# LED_Sensor_Board.net
KiCad netlist of a schematic drawn in EAGLE
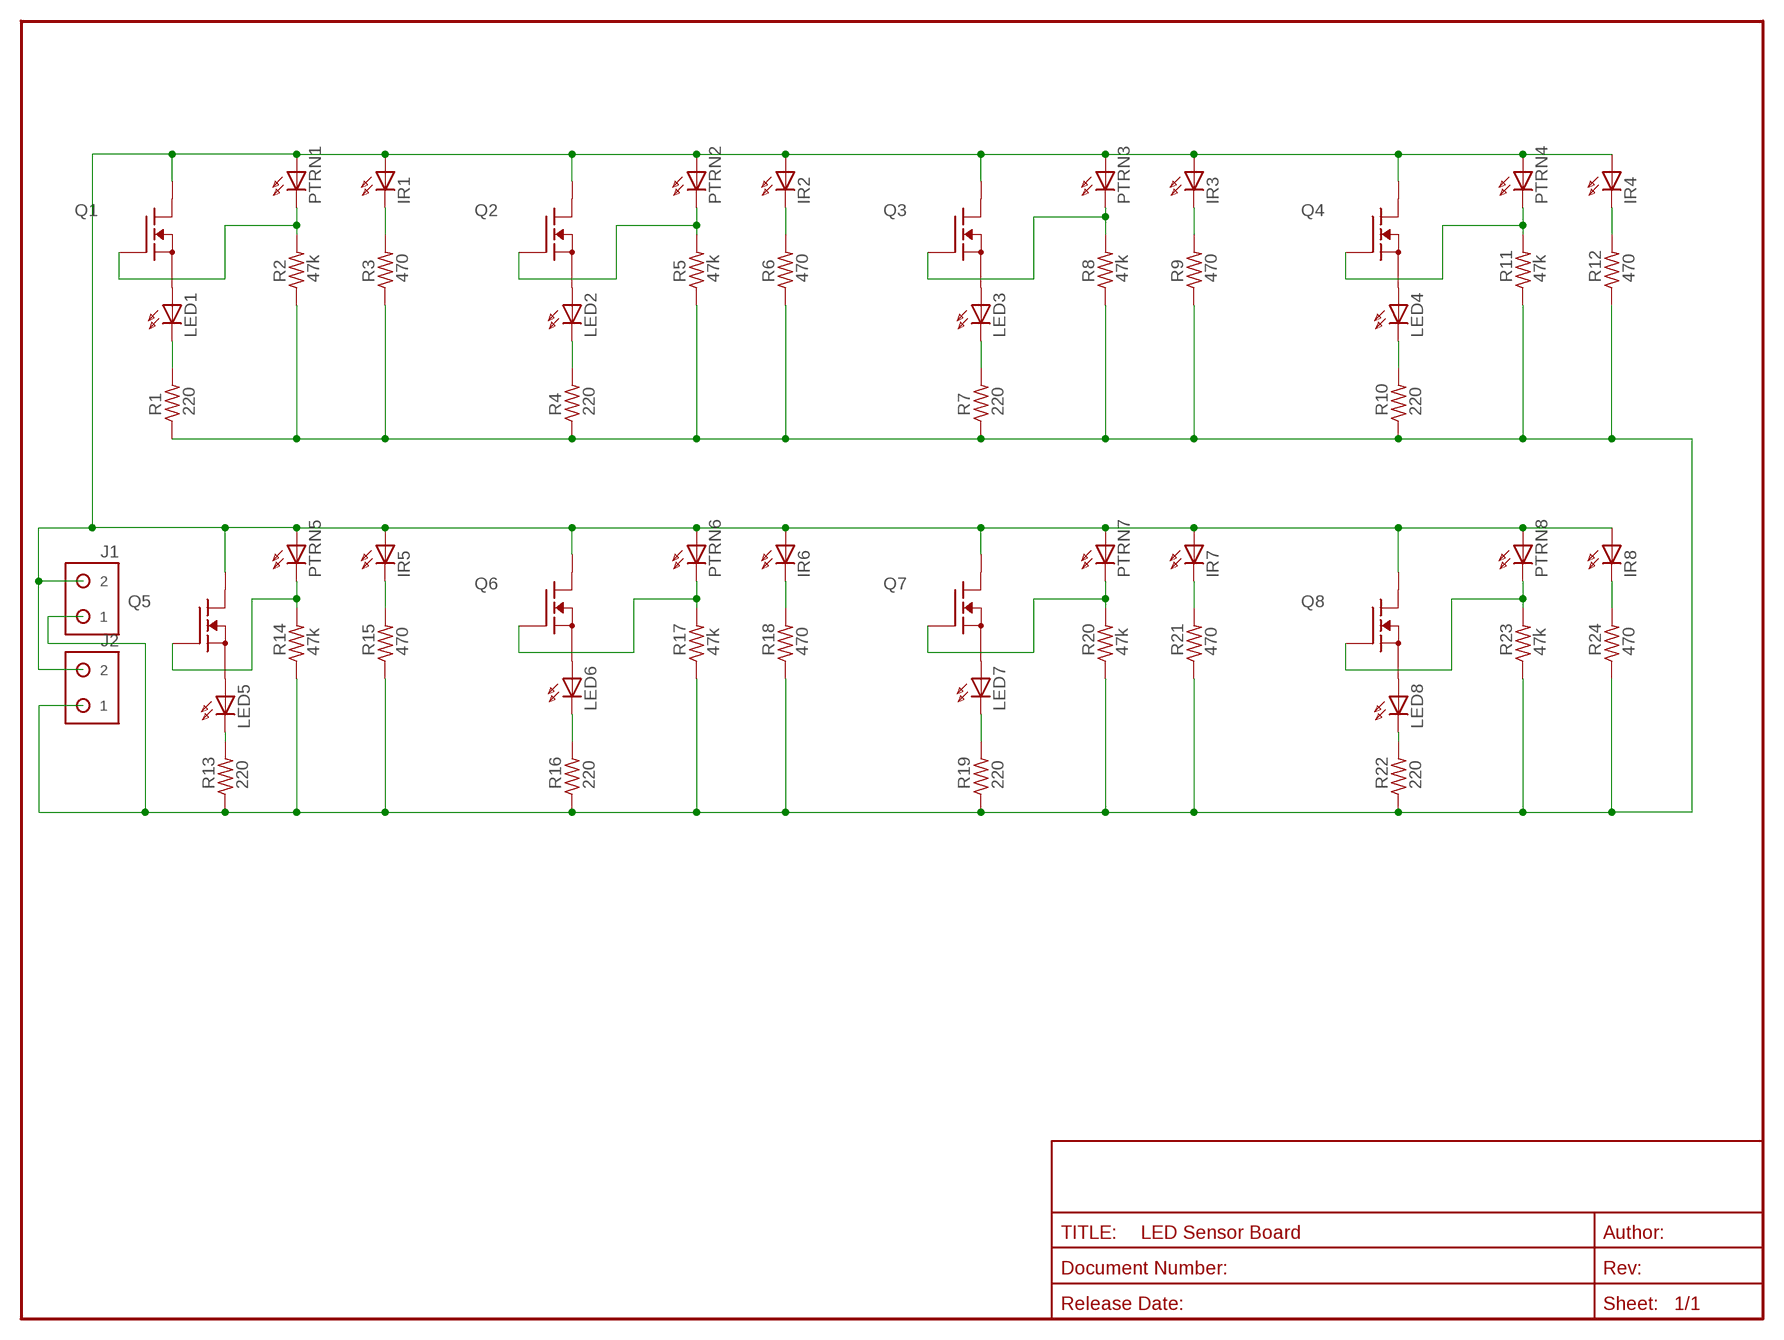
[diagram p0: schematic, sheet 1]

(export (version "E")
  (design (tool "Eeschema 10.0.6"))
  (components
    (comp (ref "IR1")
      (value "LED-T1-3/4")
      (footprint "eagle-import:LED-5MM")
      (libsource (lib "eagle-import") (part "LED-T1-3/4"))
    )
    (comp (ref "IR2")
      (value "LED-T1-3/4")
      (footprint "eagle-import:LED-5MM")
      (libsource (lib "eagle-import") (part "LED-T1-3/4"))
    )
    (comp (ref "IR3")
      (value "LED-T1-3/4")
      (footprint "eagle-import:LED-5MM")
      (libsource (lib "eagle-import") (part "LED-T1-3/4"))
    )
    (comp (ref "IR4")
      (value "LED-T1-3/4")
      (footprint "eagle-import:LED-5MM")
      (libsource (lib "eagle-import") (part "LED-T1-3/4"))
    )
    (comp (ref "IR5")
      (value "LED-T1-3/4")
      (footprint "eagle-import:LED-5MM")
      (libsource (lib "eagle-import") (part "LED-T1-3/4"))
    )
    (comp (ref "IR6")
      (value "LED-T1-3/4")
      (footprint "eagle-import:LED-5MM")
      (libsource (lib "eagle-import") (part "LED-T1-3/4"))
    )
    (comp (ref "IR7")
      (value "LED-T1-3/4")
      (footprint "eagle-import:LED-5MM")
      (libsource (lib "eagle-import") (part "LED-T1-3/4"))
    )
    (comp (ref "IR8")
      (value "LED-T1-3/4")
      (footprint "eagle-import:LED-5MM")
      (libsource (lib "eagle-import") (part "LED-T1-3/4"))
    )
    (comp (ref "J1")
      (value "HDR-1X2")
      (footprint "eagle-import:HDR-1X2")
      (libsource (lib "eagle-import") (part "HDR-1X2"))
    )
    (comp (ref "J2")
      (value "HDR-1X2")
      (footprint "eagle-import:HDR-1X2")
      (libsource (lib "eagle-import") (part "HDR-1X2"))
    )
    (comp (ref "LED1")
      (value "LED-T1-3/4")
      (footprint "eagle-import:LED-5MM")
      (libsource (lib "eagle-import") (part "LED-T1-3/4"))
    )
    (comp (ref "LED2")
      (value "LED-T1-3/4")
      (footprint "eagle-import:LED-5MM")
      (libsource (lib "eagle-import") (part "LED-T1-3/4"))
    )
    (comp (ref "LED3")
      (value "LED-T1-3/4")
      (footprint "eagle-import:LED-5MM")
      (libsource (lib "eagle-import") (part "LED-T1-3/4"))
    )
    (comp (ref "LED4")
      (value "LED-T1-3/4")
      (footprint "eagle-import:LED-5MM")
      (libsource (lib "eagle-import") (part "LED-T1-3/4"))
    )
    (comp (ref "LED5")
      (value "LED-T1-3/4")
      (footprint "eagle-import:LED-5MM")
      (libsource (lib "eagle-import") (part "LED-T1-3/4"))
    )
    (comp (ref "LED6")
      (value "LED-T1-3/4")
      (footprint "eagle-import:LED-5MM")
      (libsource (lib "eagle-import") (part "LED-T1-3/4"))
    )
    (comp (ref "LED7")
      (value "LED-T1-3/4")
      (footprint "eagle-import:LED-5MM")
      (libsource (lib "eagle-import") (part "LED-T1-3/4"))
    )
    (comp (ref "LED8")
      (value "LED-T1-3/4")
      (footprint "eagle-import:LED-5MM")
      (libsource (lib "eagle-import") (part "LED-T1-3/4"))
    )
    (comp (ref "PTRN1")
      (value "LED-T1-3/4")
      (footprint "eagle-import:LED-5MM")
      (libsource (lib "eagle-import") (part "LED-T1-3/4"))
    )
    (comp (ref "PTRN2")
      (value "LED-T1-3/4")
      (footprint "eagle-import:LED-5MM")
      (libsource (lib "eagle-import") (part "LED-T1-3/4"))
    )
    (comp (ref "PTRN3")
      (value "LED-T1-3/4")
      (footprint "eagle-import:LED-5MM")
      (libsource (lib "eagle-import") (part "LED-T1-3/4"))
    )
    (comp (ref "PTRN4")
      (value "LED-T1-3/4")
      (footprint "eagle-import:LED-5MM")
      (libsource (lib "eagle-import") (part "LED-T1-3/4"))
    )
    (comp (ref "PTRN5")
      (value "LED-T1-3/4")
      (footprint "eagle-import:LED-5MM")
      (libsource (lib "eagle-import") (part "LED-T1-3/4"))
    )
    (comp (ref "PTRN6")
      (value "LED-T1-3/4")
      (footprint "eagle-import:LED-5MM")
      (libsource (lib "eagle-import") (part "LED-T1-3/4"))
    )
    (comp (ref "PTRN7")
      (value "LED-T1-3/4")
      (footprint "eagle-import:LED-5MM")
      (libsource (lib "eagle-import") (part "LED-T1-3/4"))
    )
    (comp (ref "PTRN8")
      (value "LED-T1-3/4")
      (footprint "eagle-import:LED-5MM")
      (libsource (lib "eagle-import") (part "LED-T1-3/4"))
    )
    (comp (ref "Q1")
      (value "ZVN2110A")
      (footprint "eagle-import:TO92-")
      (libsource (lib "eagle-import") (part "ZVN2110A"))
    )
    (comp (ref "Q2")
      (value "ZVN2110A")
      (footprint "eagle-import:TO92-")
      (libsource (lib "eagle-import") (part "ZVN2110A"))
    )
    (comp (ref "Q3")
      (value "ZVN2110A")
      (footprint "eagle-import:TO92-")
      (libsource (lib "eagle-import") (part "ZVN2110A"))
    )
    (comp (ref "Q4")
      (value "ZVN2110A")
      (footprint "eagle-import:TO92-")
      (libsource (lib "eagle-import") (part "ZVN2110A"))
    )
    (comp (ref "Q5")
      (value "ZVN2110A")
      (footprint "eagle-import:TO92-")
      (libsource (lib "eagle-import") (part "ZVN2110A"))
    )
    (comp (ref "Q6")
      (value "ZVN2110A")
      (footprint "eagle-import:TO92-")
      (libsource (lib "eagle-import") (part "ZVN2110A"))
    )
    (comp (ref "Q7")
      (value "ZVN2110A")
      (footprint "eagle-import:TO92-")
      (libsource (lib "eagle-import") (part "ZVN2110A"))
    )
    (comp (ref "Q8")
      (value "ZVN2110A")
      (footprint "eagle-import:TO92-")
      (libsource (lib "eagle-import") (part "ZVN2110A"))
    )
    (comp (ref "R1")
      (value "220")
      (footprint "eagle-import:0207_10")
      (libsource (lib "eagle-import") (part "RES-0207/10"))
    )
    (comp (ref "R2")
      (value "47k")
      (footprint "eagle-import:0207_10")
      (libsource (lib "eagle-import") (part "RES-0207/10"))
    )
    (comp (ref "R3")
      (value "470")
      (footprint "eagle-import:0207_10")
      (libsource (lib "eagle-import") (part "RES-0207/10"))
    )
    (comp (ref "R4")
      (value "220")
      (footprint "eagle-import:0207_10")
      (libsource (lib "eagle-import") (part "RES-0207/10"))
    )
    (comp (ref "R5")
      (value "47k")
      (footprint "eagle-import:0207_10")
      (libsource (lib "eagle-import") (part "RES-0207/10"))
    )
    (comp (ref "R6")
      (value "470")
      (footprint "eagle-import:0207_10")
      (libsource (lib "eagle-import") (part "RES-0207/10"))
    )
    (comp (ref "R7")
      (value "220")
      (footprint "eagle-import:0207_10")
      (libsource (lib "eagle-import") (part "RES-0207/10"))
    )
    (comp (ref "R8")
      (value "47k")
      (footprint "eagle-import:0207_10")
      (libsource (lib "eagle-import") (part "RES-0207/10"))
    )
    (comp (ref "R9")
      (value "470")
      (footprint "eagle-import:0207_10")
      (libsource (lib "eagle-import") (part "RES-0207/10"))
    )
    (comp (ref "R10")
      (value "220")
      (footprint "eagle-import:0207_10")
      (libsource (lib "eagle-import") (part "RES-0207/10"))
    )
    (comp (ref "R11")
      (value "47k")
      (footprint "eagle-import:0207_10")
      (libsource (lib "eagle-import") (part "RES-0207/10"))
    )
    (comp (ref "R12")
      (value "470")
      (footprint "eagle-import:0207_10")
      (libsource (lib "eagle-import") (part "RES-0207/10"))
    )
    (comp (ref "R13")
      (value "220")
      (footprint "eagle-import:0207_10")
      (libsource (lib "eagle-import") (part "RES-0207/10"))
    )
    (comp (ref "R14")
      (value "47k")
      (footprint "eagle-import:0207_10")
      (libsource (lib "eagle-import") (part "RES-0207/10"))
    )
    (comp (ref "R15")
      (value "470")
      (footprint "eagle-import:0207_10")
      (libsource (lib "eagle-import") (part "RES-0207/10"))
    )
    (comp (ref "R16")
      (value "220")
      (footprint "eagle-import:0207_10")
      (libsource (lib "eagle-import") (part "RES-0207/10"))
    )
    (comp (ref "R17")
      (value "47k")
      (footprint "eagle-import:0207_10")
      (libsource (lib "eagle-import") (part "RES-0207/10"))
    )
    (comp (ref "R18")
      (value "470")
      (footprint "eagle-import:0207_10")
      (libsource (lib "eagle-import") (part "RES-0207/10"))
    )
    (comp (ref "R19")
      (value "220")
      (footprint "eagle-import:0207_10")
      (libsource (lib "eagle-import") (part "RES-0207/10"))
    )
    (comp (ref "R20")
      (value "47k")
      (footprint "eagle-import:0207_10")
      (libsource (lib "eagle-import") (part "RES-0207/10"))
    )
    (comp (ref "R21")
      (value "470")
      (footprint "eagle-import:0207_10")
      (libsource (lib "eagle-import") (part "RES-0207/10"))
    )
    (comp (ref "R22")
      (value "220")
      (footprint "eagle-import:0207_10")
      (libsource (lib "eagle-import") (part "RES-0207/10"))
    )
    (comp (ref "R23")
      (value "47k")
      (footprint "eagle-import:0207_10")
      (libsource (lib "eagle-import") (part "RES-0207/10"))
    )
    (comp (ref "R24")
      (value "470")
      (footprint "eagle-import:0207_10")
      (libsource (lib "eagle-import") (part "RES-0207/10"))
    )
  )
  (nets
    (net (code "1") (name "Net-(IR1-C)") (class "Default")
      (node (ref "IR1") (pin "K") (pinfunction "C_K") (pintype "passive"))
      (node (ref "R3") (pin "2") (pinfunction "2_2") (pintype "passive"))
    )
    (net (code "2") (name "Net-(IR2-C)") (class "Default")
      (node (ref "IR2") (pin "K") (pinfunction "C_K") (pintype "passive"))
      (node (ref "R6") (pin "2") (pinfunction "2_2") (pintype "passive"))
    )
    (net (code "3") (name "Net-(IR3-C)") (class "Default")
      (node (ref "IR3") (pin "K") (pinfunction "C_K") (pintype "passive"))
      (node (ref "R9") (pin "2") (pinfunction "2_2") (pintype "passive"))
    )
    (net (code "4") (name "Net-(IR4-C)") (class "Default")
      (node (ref "IR4") (pin "K") (pinfunction "C_K") (pintype "passive"))
      (node (ref "R12") (pin "2") (pinfunction "2_2") (pintype "passive"))
    )
    (net (code "5") (name "Net-(IR5-C)") (class "Default")
      (node (ref "IR5") (pin "K") (pinfunction "C_K") (pintype "passive"))
      (node (ref "R15") (pin "2") (pinfunction "2_2") (pintype "passive"))
    )
    (net (code "6") (name "Net-(IR6-C)") (class "Default")
      (node (ref "IR6") (pin "K") (pinfunction "C_K") (pintype "passive"))
      (node (ref "R18") (pin "2") (pinfunction "2_2") (pintype "passive"))
    )
    (net (code "7") (name "Net-(IR7-C)") (class "Default")
      (node (ref "IR7") (pin "K") (pinfunction "C_K") (pintype "passive"))
      (node (ref "R21") (pin "2") (pinfunction "2_2") (pintype "passive"))
    )
    (net (code "8") (name "Net-(IR8-C)") (class "Default")
      (node (ref "IR8") (pin "K") (pinfunction "C_K") (pintype "passive"))
      (node (ref "R24") (pin "2") (pinfunction "2_2") (pintype "passive"))
    )
    (net (code "9") (name "Net-(J1-Pad1)") (class "Default")
      (node (ref "J1") (pin "1") (pinfunction "1_1") (pintype "passive"))
      (node (ref "J2") (pin "1") (pinfunction "1_1") (pintype "passive"))
      (node (ref "R1") (pin "1") (pinfunction "1_1") (pintype "passive"))
      (node (ref "R10") (pin "1") (pinfunction "1_1") (pintype "passive"))
      (node (ref "R11") (pin "1") (pinfunction "1_1") (pintype "passive"))
      (node (ref "R12") (pin "1") (pinfunction "1_1") (pintype "passive"))
      (node (ref "R13") (pin "1") (pinfunction "1_1") (pintype "passive"))
      (node (ref "R14") (pin "1") (pinfunction "1_1") (pintype "passive"))
      (node (ref "R15") (pin "1") (pinfunction "1_1") (pintype "passive"))
      (node (ref "R16") (pin "1") (pinfunction "1_1") (pintype "passive"))
      (node (ref "R17") (pin "1") (pinfunction "1_1") (pintype "passive"))
      (node (ref "R18") (pin "1") (pinfunction "1_1") (pintype "passive"))
      (node (ref "R19") (pin "1") (pinfunction "1_1") (pintype "passive"))
      (node (ref "R2") (pin "1") (pinfunction "1_1") (pintype "passive"))
      (node (ref "R20") (pin "1") (pinfunction "1_1") (pintype "passive"))
      (node (ref "R21") (pin "1") (pinfunction "1_1") (pintype "passive"))
      (node (ref "R22") (pin "1") (pinfunction "1_1") (pintype "passive"))
      (node (ref "R23") (pin "1") (pinfunction "1_1") (pintype "passive"))
      (node (ref "R24") (pin "1") (pinfunction "1_1") (pintype "passive"))
      (node (ref "R3") (pin "1") (pinfunction "1_1") (pintype "passive"))
      (node (ref "R4") (pin "1") (pinfunction "1_1") (pintype "passive"))
      (node (ref "R5") (pin "1") (pinfunction "1_1") (pintype "passive"))
      (node (ref "R6") (pin "1") (pinfunction "1_1") (pintype "passive"))
      (node (ref "R7") (pin "1") (pinfunction "1_1") (pintype "passive"))
      (node (ref "R8") (pin "1") (pinfunction "1_1") (pintype "passive"))
      (node (ref "R9") (pin "1") (pinfunction "1_1") (pintype "passive"))
    )
    (net (code "10") (name "Net-(LED1-C)") (class "Default")
      (node (ref "LED1") (pin "K") (pinfunction "C_K") (pintype "passive"))
      (node (ref "R1") (pin "2") (pinfunction "2_2") (pintype "passive"))
    )
    (net (code "11") (name "Net-(LED2-C)") (class "Default")
      (node (ref "LED2") (pin "K") (pinfunction "C_K") (pintype "passive"))
      (node (ref "R4") (pin "2") (pinfunction "2_2") (pintype "passive"))
    )
    (net (code "12") (name "Net-(LED3-C)") (class "Default")
      (node (ref "LED3") (pin "K") (pinfunction "C_K") (pintype "passive"))
      (node (ref "R7") (pin "2") (pinfunction "2_2") (pintype "passive"))
    )
    (net (code "13") (name "Net-(LED4-C)") (class "Default")
      (node (ref "LED4") (pin "K") (pinfunction "C_K") (pintype "passive"))
      (node (ref "R10") (pin "2") (pinfunction "2_2") (pintype "passive"))
    )
    (net (code "14") (name "Net-(LED5-C)") (class "Default")
      (node (ref "LED5") (pin "K") (pinfunction "C_K") (pintype "passive"))
      (node (ref "R13") (pin "2") (pinfunction "2_2") (pintype "passive"))
    )
    (net (code "15") (name "Net-(LED6-C)") (class "Default")
      (node (ref "LED6") (pin "K") (pinfunction "C_K") (pintype "passive"))
      (node (ref "R16") (pin "2") (pinfunction "2_2") (pintype "passive"))
    )
    (net (code "16") (name "Net-(LED7-C)") (class "Default")
      (node (ref "LED7") (pin "K") (pinfunction "C_K") (pintype "passive"))
      (node (ref "R19") (pin "2") (pinfunction "2_2") (pintype "passive"))
    )
    (net (code "17") (name "Net-(LED8-C)") (class "Default")
      (node (ref "LED8") (pin "K") (pinfunction "C_K") (pintype "passive"))
      (node (ref "R22") (pin "2") (pinfunction "2_2") (pintype "passive"))
    )
    (net (code "18") (name "Net-(PTRN1-C)") (class "Default")
      (node (ref "PTRN1") (pin "K") (pinfunction "C_K") (pintype "passive"))
      (node (ref "Q1") (pin "2") (pinfunction "G_2") (pintype "passive"))
      (node (ref "R2") (pin "2") (pinfunction "2_2") (pintype "passive"))
    )
    (net (code "19") (name "Net-(PTRN2-C)") (class "Default")
      (node (ref "PTRN2") (pin "K") (pinfunction "C_K") (pintype "passive"))
      (node (ref "Q2") (pin "2") (pinfunction "G_2") (pintype "passive"))
      (node (ref "R5") (pin "2") (pinfunction "2_2") (pintype "passive"))
    )
    (net (code "20") (name "Net-(PTRN3-C)") (class "Default")
      (node (ref "PTRN3") (pin "K") (pinfunction "C_K") (pintype "passive"))
      (node (ref "Q3") (pin "2") (pinfunction "G_2") (pintype "passive"))
      (node (ref "R8") (pin "2") (pinfunction "2_2") (pintype "passive"))
    )
    (net (code "21") (name "Net-(PTRN4-C)") (class "Default")
      (node (ref "PTRN4") (pin "K") (pinfunction "C_K") (pintype "passive"))
      (node (ref "Q4") (pin "2") (pinfunction "G_2") (pintype "passive"))
      (node (ref "R11") (pin "2") (pinfunction "2_2") (pintype "passive"))
    )
    (net (code "22") (name "Net-(PTRN5-C)") (class "Default")
      (node (ref "PTRN5") (pin "K") (pinfunction "C_K") (pintype "passive"))
      (node (ref "Q5") (pin "2") (pinfunction "G_2") (pintype "passive"))
      (node (ref "R14") (pin "2") (pinfunction "2_2") (pintype "passive"))
    )
    (net (code "23") (name "Net-(PTRN6-C)") (class "Default")
      (node (ref "PTRN6") (pin "K") (pinfunction "C_K") (pintype "passive"))
      (node (ref "Q6") (pin "2") (pinfunction "G_2") (pintype "passive"))
      (node (ref "R17") (pin "2") (pinfunction "2_2") (pintype "passive"))
    )
    (net (code "24") (name "Net-(PTRN7-C)") (class "Default")
      (node (ref "PTRN7") (pin "K") (pinfunction "C_K") (pintype "passive"))
      (node (ref "Q7") (pin "2") (pinfunction "G_2") (pintype "passive"))
      (node (ref "R20") (pin "2") (pinfunction "2_2") (pintype "passive"))
    )
    (net (code "25") (name "Net-(PTRN8-C)") (class "Default")
      (node (ref "PTRN8") (pin "K") (pinfunction "C_K") (pintype "passive"))
      (node (ref "Q8") (pin "2") (pinfunction "G_2") (pintype "passive"))
      (node (ref "R23") (pin "2") (pinfunction "2_2") (pintype "passive"))
    )
    (net (code "26") (name "Net-(Q1-D)") (class "Default")
      (node (ref "IR1") (pin "A") (pinfunction "A_A") (pintype "passive"))
      (node (ref "IR2") (pin "A") (pinfunction "A_A") (pintype "passive"))
      (node (ref "IR3") (pin "A") (pinfunction "A_A") (pintype "passive"))
      (node (ref "IR4") (pin "A") (pinfunction "A_A") (pintype "passive"))
      (node (ref "IR5") (pin "A") (pinfunction "A_A") (pintype "passive"))
      (node (ref "IR6") (pin "A") (pinfunction "A_A") (pintype "passive"))
      (node (ref "IR7") (pin "A") (pinfunction "A_A") (pintype "passive"))
      (node (ref "IR8") (pin "A") (pinfunction "A_A") (pintype "passive"))
      (node (ref "J1") (pin "2") (pinfunction "2_2") (pintype "passive"))
      (node (ref "J2") (pin "2") (pinfunction "2_2") (pintype "passive"))
      (node (ref "PTRN1") (pin "A") (pinfunction "A_A") (pintype "passive"))
      (node (ref "PTRN2") (pin "A") (pinfunction "A_A") (pintype "passive"))
      (node (ref "PTRN3") (pin "A") (pinfunction "A_A") (pintype "passive"))
      (node (ref "PTRN4") (pin "A") (pinfunction "A_A") (pintype "passive"))
      (node (ref "PTRN5") (pin "A") (pinfunction "A_A") (pintype "passive"))
      (node (ref "PTRN6") (pin "A") (pinfunction "A_A") (pintype "passive"))
      (node (ref "PTRN7") (pin "A") (pinfunction "A_A") (pintype "passive"))
      (node (ref "PTRN8") (pin "A") (pinfunction "A_A") (pintype "passive"))
      (node (ref "Q1") (pin "1") (pinfunction "D_1") (pintype "passive"))
      (node (ref "Q2") (pin "1") (pinfunction "D_1") (pintype "passive"))
      (node (ref "Q3") (pin "1") (pinfunction "D_1") (pintype "passive"))
      (node (ref "Q4") (pin "1") (pinfunction "D_1") (pintype "passive"))
      (node (ref "Q5") (pin "1") (pinfunction "D_1") (pintype "passive"))
      (node (ref "Q6") (pin "1") (pinfunction "D_1") (pintype "passive"))
      (node (ref "Q7") (pin "1") (pinfunction "D_1") (pintype "passive"))
      (node (ref "Q8") (pin "1") (pinfunction "D_1") (pintype "passive"))
    )
    (net (code "27") (name "Net-(Q1-S)") (class "Default")
      (node (ref "LED1") (pin "A") (pinfunction "A_A") (pintype "passive"))
      (node (ref "Q1") (pin "3") (pinfunction "S_3") (pintype "passive"))
    )
    (net (code "28") (name "Net-(Q2-S)") (class "Default")
      (node (ref "LED2") (pin "A") (pinfunction "A_A") (pintype "passive"))
      (node (ref "Q2") (pin "3") (pinfunction "S_3") (pintype "passive"))
    )
    (net (code "29") (name "Net-(Q3-S)") (class "Default")
      (node (ref "LED3") (pin "A") (pinfunction "A_A") (pintype "passive"))
      (node (ref "Q3") (pin "3") (pinfunction "S_3") (pintype "passive"))
    )
    (net (code "30") (name "Net-(Q4-S)") (class "Default")
      (node (ref "LED4") (pin "A") (pinfunction "A_A") (pintype "passive"))
      (node (ref "Q4") (pin "3") (pinfunction "S_3") (pintype "passive"))
    )
    (net (code "31") (name "Net-(Q5-S)") (class "Default")
      (node (ref "LED5") (pin "A") (pinfunction "A_A") (pintype "passive"))
      (node (ref "Q5") (pin "3") (pinfunction "S_3") (pintype "passive"))
    )
    (net (code "32") (name "Net-(Q6-S)") (class "Default")
      (node (ref "LED6") (pin "A") (pinfunction "A_A") (pintype "passive"))
      (node (ref "Q6") (pin "3") (pinfunction "S_3") (pintype "passive"))
    )
    (net (code "33") (name "Net-(Q7-S)") (class "Default")
      (node (ref "LED7") (pin "A") (pinfunction "A_A") (pintype "passive"))
      (node (ref "Q7") (pin "3") (pinfunction "S_3") (pintype "passive"))
    )
    (net (code "34") (name "Net-(Q8-S)") (class "Default")
      (node (ref "LED8") (pin "A") (pinfunction "A_A") (pintype "passive"))
      (node (ref "Q8") (pin "3") (pinfunction "S_3") (pintype "passive"))
    )
  )
)
